# led_pack32_touch.net
KiCad netlist of a schematic drawn in Altium Designer
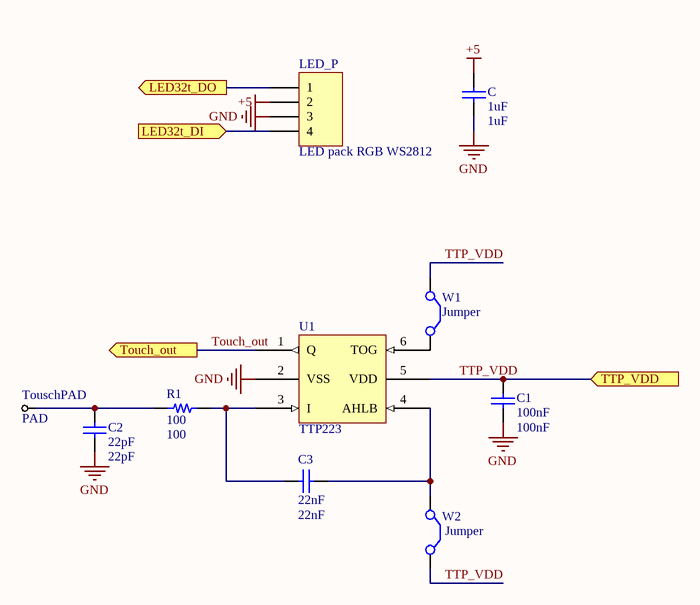
[diagram p0: led_pack32_touch.SchDoc]

(export (version "E")
  (design (tool "Eeschema 10.0.6"))
  (components
    (comp (ref "C")
      (value "1uF")
      (footprint "0603C")
      (description "CAP SMD 0603")
      (fields (field (name "ALTIUM_VALUE") "1uF") (field (name "PUBLISHER") "Altium Limited"))
      (libsource (lib "Miscellaneous Devices") (part "Cap"))
    )
    (comp (ref "C1")
      (value "100nF")
      (footprint "0603C")
      (description "CAP SMD 0603")
      (fields (field (name "ALTIUM_VALUE") "100nF") (field (name "PUBLISHER") "Altium Limited"))
      (libsource (lib "Miscellaneous Devices") (part "Cap"))
    )
    (comp (ref "C2")
      (value "22pF")
      (footprint "0603C")
      (description "X7R_NPO")
      (fields (field (name "ALTIUM_VALUE") "22pF") (field (name "PUBLISHER") "Altium Limited"))
      (libsource (lib "Miscellaneous Devices") (part "Cap"))
    )
    (comp (ref "C3")
      (value "22nF")
      (footprint "0603C")
      (description "X7R_NPO")
      (fields (field (name "ALTIUM_VALUE") "22nF") (field (name "PUBLISHER") "Altium Limited"))
      (libsource (lib "Miscellaneous Devices") (part "Cap"))
    )
    (comp (ref "LED_P")
      (value "LED pack RGB WS2812")
      (footprint "PACK32-2121")
      (description "8 32mm RGB LED pack")
      (fields (field (name "PUBLISHER") "Altium Limited"))
      (libsource (lib "Altium") (part "Header 4"))
    )
    (comp (ref "PAD")
      (value "TouschPAD")
      (footprint "touchPAD4")
      (libsource (lib "Altium (2)") (part "Test Point"))
    )
    (comp (ref "R1")
      (value "100")
      (footprint "0603R")
      (description "RES SMD 0603")
      (fields (field (name "PART NUMBER") "RCS0805100KFKEA") (field (name "ALTIUM_VALUE") "100"))
      (libsource (lib "lamp control-ver2") (part "Resistor"))
    )
    (comp (ref "U1")
      (value "TTP223")
      (footprint "SOT23-6_L")
      (description "capacitive touch IC")
      (libsource (lib "Schlib1") (part "ttp223b"))
    )
    (comp (ref "W1")
      (value "Jumper")
      (footprint "JUMPER")
      (description "Jumper Wire")
      (fields (field (name "PUBLISHER") "Altium Limited"))
      (libsource (lib "Miscellaneous Devices") (part "Jumper"))
    )
    (comp (ref "W2")
      (value "Jumper")
      (footprint "JUMPER")
      (description "Jumper Wire")
      (fields (field (name "PUBLISHER") "Altium Limited"))
      (libsource (lib "Miscellaneous Devices") (part "Jumper"))
    )
  )
  (nets
    (net (code "1") (name "+5") (class "Default")
      (node (ref "C") (pin "2") (pinfunction "2_2") (pintype "passive"))
      (node (ref "LED_P") (pin "2") (pinfunction "2_2") (pintype "passive"))
    )
    (net (code "2") (name "/LED32t_DI") (class "Default")
      (node (ref "LED_P") (pin "4") (pinfunction "4_4") (pintype "passive"))
    )
    (net (code "3") (name "/LED32t_DO") (class "Default")
      (node (ref "LED_P") (pin "1") (pinfunction "1_1") (pintype "passive"))
    )
    (net (code "4") (name "/TTP_VDD") (class "Default")
      (node (ref "C1") (pin "2") (pinfunction "2_2") (pintype "passive"))
      (node (ref "U1") (pin "5") (pinfunction "VDD_5") (pintype "power_in"))
      (node (ref "W1") (pin "1") (pinfunction "C1_1") (pintype "passive"))
      (node (ref "W2") (pin "2") (pinfunction "C2_2") (pintype "passive"))
    )
    (net (code "5") (name "/Touch_out") (class "Default")
      (node (ref "U1") (pin "1") (pinfunction "Q_1") (pintype "output"))
    )
    (net (code "6") (name "GND") (class "Default")
      (node (ref "C") (pin "1") (pinfunction "1_1") (pintype "passive"))
      (node (ref "C1") (pin "1") (pinfunction "1_1") (pintype "passive"))
      (node (ref "C2") (pin "1") (pinfunction "1_1") (pintype "passive"))
      (node (ref "LED_P") (pin "3") (pinfunction "3_3") (pintype "passive"))
      (node (ref "U1") (pin "2") (pinfunction "VSS_2") (pintype "power_in"))
    )
    (net (code "7") (name "Net-(PAD-T)") (class "Default")
      (node (ref "C2") (pin "2") (pinfunction "2_2") (pintype "passive"))
      (node (ref "PAD") (pin "1") (pinfunction "T_1") (pintype "passive"))
      (node (ref "R1") (pin "2") (pinfunction "2_2") (pintype "passive"))
    )
    (net (code "8") (name "Net-(U1-AHLB)") (class "Default")
      (node (ref "C3") (pin "1") (pinfunction "1_1") (pintype "passive"))
      (node (ref "U1") (pin "4") (pinfunction "AHLB_4") (pintype "input"))
      (node (ref "W2") (pin "1") (pinfunction "C1_1") (pintype "passive"))
    )
    (net (code "9") (name "Net-(U1-I)") (class "Default")
      (node (ref "C3") (pin "2") (pinfunction "2_2") (pintype "passive"))
      (node (ref "R1") (pin "1") (pinfunction "1_1") (pintype "passive"))
      (node (ref "U1") (pin "3") (pinfunction "I_3") (pintype "input"))
    )
    (net (code "10") (name "Net-(U1-TOG)") (class "Default")
      (node (ref "U1") (pin "6") (pinfunction "TOG_6") (pintype "input"))
      (node (ref "W1") (pin "2") (pinfunction "C2_2") (pintype "passive"))
    )
  )
)
